# Core_LCD_Shield.net
KiCad netlist of a schematic drawn in EAGLE
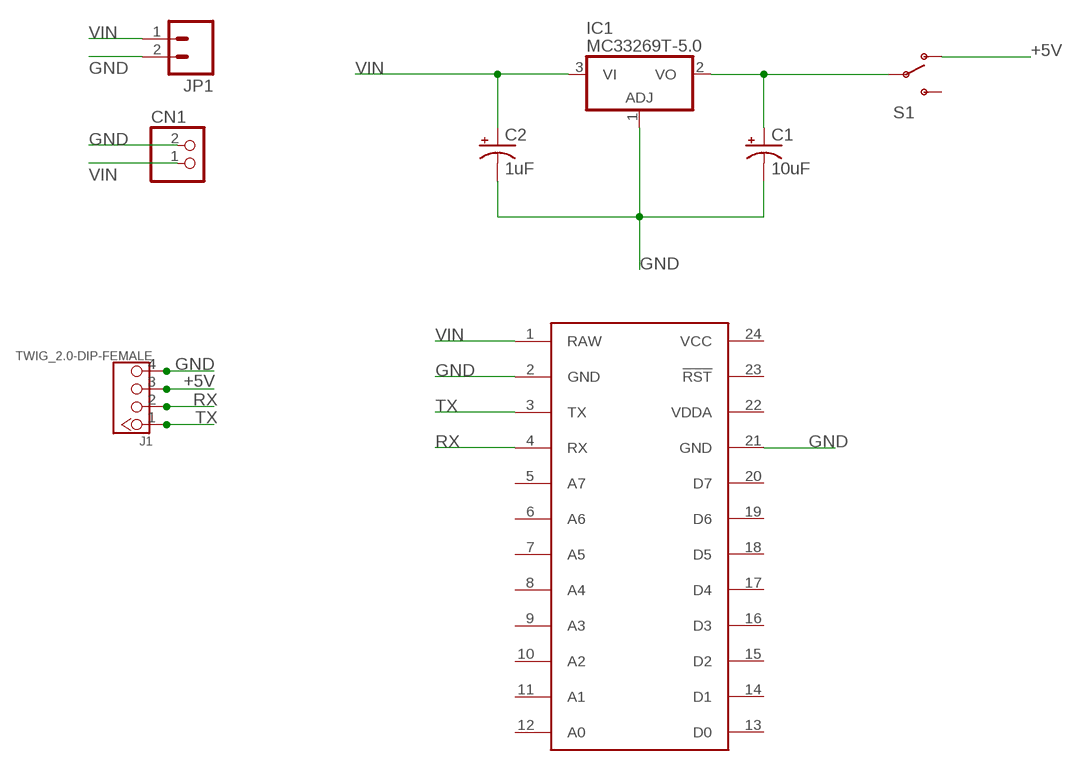
[diagram p0: schematic, sheet 1]

(export (version "E")
  (design (tool "Eeschema 10.0.6"))
  (components
    (comp (ref "C1")
      (value "10uF")
      (footprint "eagle-import:CPOL-RADIAL-10UF-25V")
      (libsource (lib "eagle-import") (part "CAP_POLPTH2"))
    )
    (comp (ref "C2")
      (value "1uF")
      (footprint "eagle-import:CPOL-RADIAL-10UF-25V")
      (libsource (lib "eagle-import") (part "CAP_POLPTH2"))
    )
    (comp (ref "CN1")
      (value "JST_2PIN-THM")
      (footprint "eagle-import:JST-PH-2-THM")
      (libsource (lib "eagle-import") (part "JST_2PIN-THM"))
    )
    (comp (ref "IC1")
      (value "MC33269T-5.0")
      (footprint "eagle-import:TO220V")
      (libsource (lib "eagle-import") (part "MC33269?T-5.0"))
    )
    (comp (ref "J1")
      (value "TWIG_2.0-DIP-FEMALE")
      (footprint "eagle-import:2.0_1X4")
      (libsource (lib "eagle-import") (part "TWIG_2.0-DIP-FEMALE"))
    )
    (comp (ref "JP1")
      (value "M02LOCK")
      (footprint "eagle-import:1X02_LOCK")
      (libsource (lib "eagle-import") (part "M02LOCK"))
    )
    (comp (ref "S1")
      (value "SWITCH-SPDTPTH")
      (footprint "eagle-import:SWITCH-SPDT")
      (libsource (lib "eagle-import") (part "SWITCH-SPDTPTH"))
    )
    (comp (ref "U$1")
      (value "SPARK_CORECORE")
      (footprint "eagle-import:SPARK_CORE")
      (libsource (lib "eagle-import") (part "SPARK_CORECORE"))
    )
  )
  (nets
    (net (code "1") (name "/+5V") (class "Default")
      (node (ref "J1") (pin "3") (pinfunction "3_3") (pintype "bidirectional"))
      (node (ref "S1") (pin "1") (pinfunction "O_1") (pintype "passive"))
    )
    (net (code "2") (name "/GND") (class "Default")
      (node (ref "C1") (pin "2") (pinfunction "-_2") (pintype "passive"))
      (node (ref "C2") (pin "2") (pinfunction "-_2") (pintype "passive"))
      (node (ref "CN1") (pin "2") (pinfunction "1_2") (pintype "passive"))
      (node (ref "IC1") (pin "1") (pinfunction "ADJ_1") (pintype "input"))
      (node (ref "J1") (pin "4") (pinfunction "4_4") (pintype "bidirectional"))
      (node (ref "JP1") (pin "2") (pinfunction "2_2") (pintype "passive"))
      (node (ref "U$1") (pin "2") (pinfunction "GND_2") (pintype "power_in"))
      (node (ref "U$1") (pin "21") (pinfunction "GND_21") (pintype "power_in"))
    )
    (net (code "3") (name "/RX") (class "Default")
      (node (ref "J1") (pin "2") (pinfunction "2_2") (pintype "bidirectional"))
      (node (ref "U$1") (pin "4") (pinfunction "RX_4") (pintype "bidirectional"))
    )
    (net (code "4") (name "/TX") (class "Default")
      (node (ref "J1") (pin "1") (pinfunction "1_1") (pintype "bidirectional"))
      (node (ref "U$1") (pin "3") (pinfunction "TX_3") (pintype "bidirectional"))
    )
    (net (code "5") (name "/VCC") (class "Default")
      (node (ref "U$1") (pin "24") (pinfunction "VCC_24") (pintype "power_in"))
    )
    (net (code "6") (name "/VDDA") (class "Default")
      (node (ref "U$1") (pin "22") (pinfunction "VDDA_22") (pintype "power_in"))
    )
    (net (code "7") (name "/VIN") (class "Default")
      (node (ref "C2") (pin "1") (pinfunction "+_1") (pintype "passive"))
      (node (ref "CN1") (pin "1") (pinfunction "2_1") (pintype "passive"))
      (node (ref "IC1") (pin "3") (pinfunction "VI_3") (pintype "input"))
      (node (ref "JP1") (pin "1") (pinfunction "1_1") (pintype "passive"))
      (node (ref "U$1") (pin "1") (pinfunction "RAW_1") (pintype "power_in"))
    )
    (net (code "8") (name "Net-(C1-+)") (class "Default")
      (node (ref "C1") (pin "1") (pinfunction "+_1") (pintype "passive"))
      (node (ref "IC1") (pin "2") (pinfunction "VO_2") (pintype "passive"))
      (node (ref "S1") (pin "2") (pinfunction "P_2") (pintype "passive"))
    )
    (net (code "9") (name "unconnected-(S1-S-Pad3)") (class "Default")
      (node (ref "S1") (pin "3") (pinfunction "S_3") (pintype "passive"))
    )
    (net (code "10") (name "unconnected-(U$1-A0-Pad12)") (class "Default")
      (node (ref "U$1") (pin "12") (pinfunction "A0_12") (pintype "bidirectional"))
    )
    (net (code "11") (name "unconnected-(U$1-A1-Pad11)") (class "Default")
      (node (ref "U$1") (pin "11") (pinfunction "A1_11") (pintype "bidirectional"))
    )
    (net (code "12") (name "unconnected-(U$1-A2-Pad10)") (class "Default")
      (node (ref "U$1") (pin "10") (pinfunction "A2_10") (pintype "bidirectional"))
    )
    (net (code "13") (name "unconnected-(U$1-A3-Pad9)") (class "Default")
      (node (ref "U$1") (pin "9") (pinfunction "A3_9") (pintype "bidirectional"))
    )
    (net (code "14") (name "unconnected-(U$1-A4-Pad8)") (class "Default")
      (node (ref "U$1") (pin "8") (pinfunction "A4_8") (pintype "bidirectional"))
    )
    (net (code "15") (name "unconnected-(U$1-A5-Pad7)") (class "Default")
      (node (ref "U$1") (pin "7") (pinfunction "A5_7") (pintype "bidirectional"))
    )
    (net (code "16") (name "unconnected-(U$1-A6-Pad6)") (class "Default")
      (node (ref "U$1") (pin "6") (pinfunction "A6_6") (pintype "bidirectional"))
    )
    (net (code "17") (name "unconnected-(U$1-A7-Pad5)") (class "Default")
      (node (ref "U$1") (pin "5") (pinfunction "A7_5") (pintype "bidirectional"))
    )
    (net (code "18") (name "unconnected-(U$1-D0-Pad13)") (class "Default")
      (node (ref "U$1") (pin "13") (pinfunction "D0_13") (pintype "bidirectional"))
    )
    (net (code "19") (name "unconnected-(U$1-D1-Pad14)") (class "Default")
      (node (ref "U$1") (pin "14") (pinfunction "D1_14") (pintype "bidirectional"))
    )
    (net (code "20") (name "unconnected-(U$1-D2-Pad15)") (class "Default")
      (node (ref "U$1") (pin "15") (pinfunction "D2_15") (pintype "bidirectional"))
    )
    (net (code "21") (name "unconnected-(U$1-D3-Pad16)") (class "Default")
      (node (ref "U$1") (pin "16") (pinfunction "D3_16") (pintype "bidirectional"))
    )
    (net (code "22") (name "unconnected-(U$1-D4-Pad17)") (class "Default")
      (node (ref "U$1") (pin "17") (pinfunction "D4_17") (pintype "bidirectional"))
    )
    (net (code "23") (name "unconnected-(U$1-D5-Pad18)") (class "Default")
      (node (ref "U$1") (pin "18") (pinfunction "D5_18") (pintype "bidirectional"))
    )
    (net (code "24") (name "unconnected-(U$1-D6-Pad19)") (class "Default")
      (node (ref "U$1") (pin "19") (pinfunction "D6_19") (pintype "bidirectional"))
    )
    (net (code "25") (name "unconnected-(U$1-D7-Pad20)") (class "Default")
      (node (ref "U$1") (pin "20") (pinfunction "D7_20") (pintype "bidirectional"))
    )
    (net (code "26") (name "unconnected-(U$1-~{RST}-Pad23)") (class "Default")
      (node (ref "U$1") (pin "23") (pinfunction "~{RST}_23") (pintype "bidirectional"))
    )
  )
)
